# PRY417_Gde.net
KiCad netlist of a schematic drawn in EAGLE
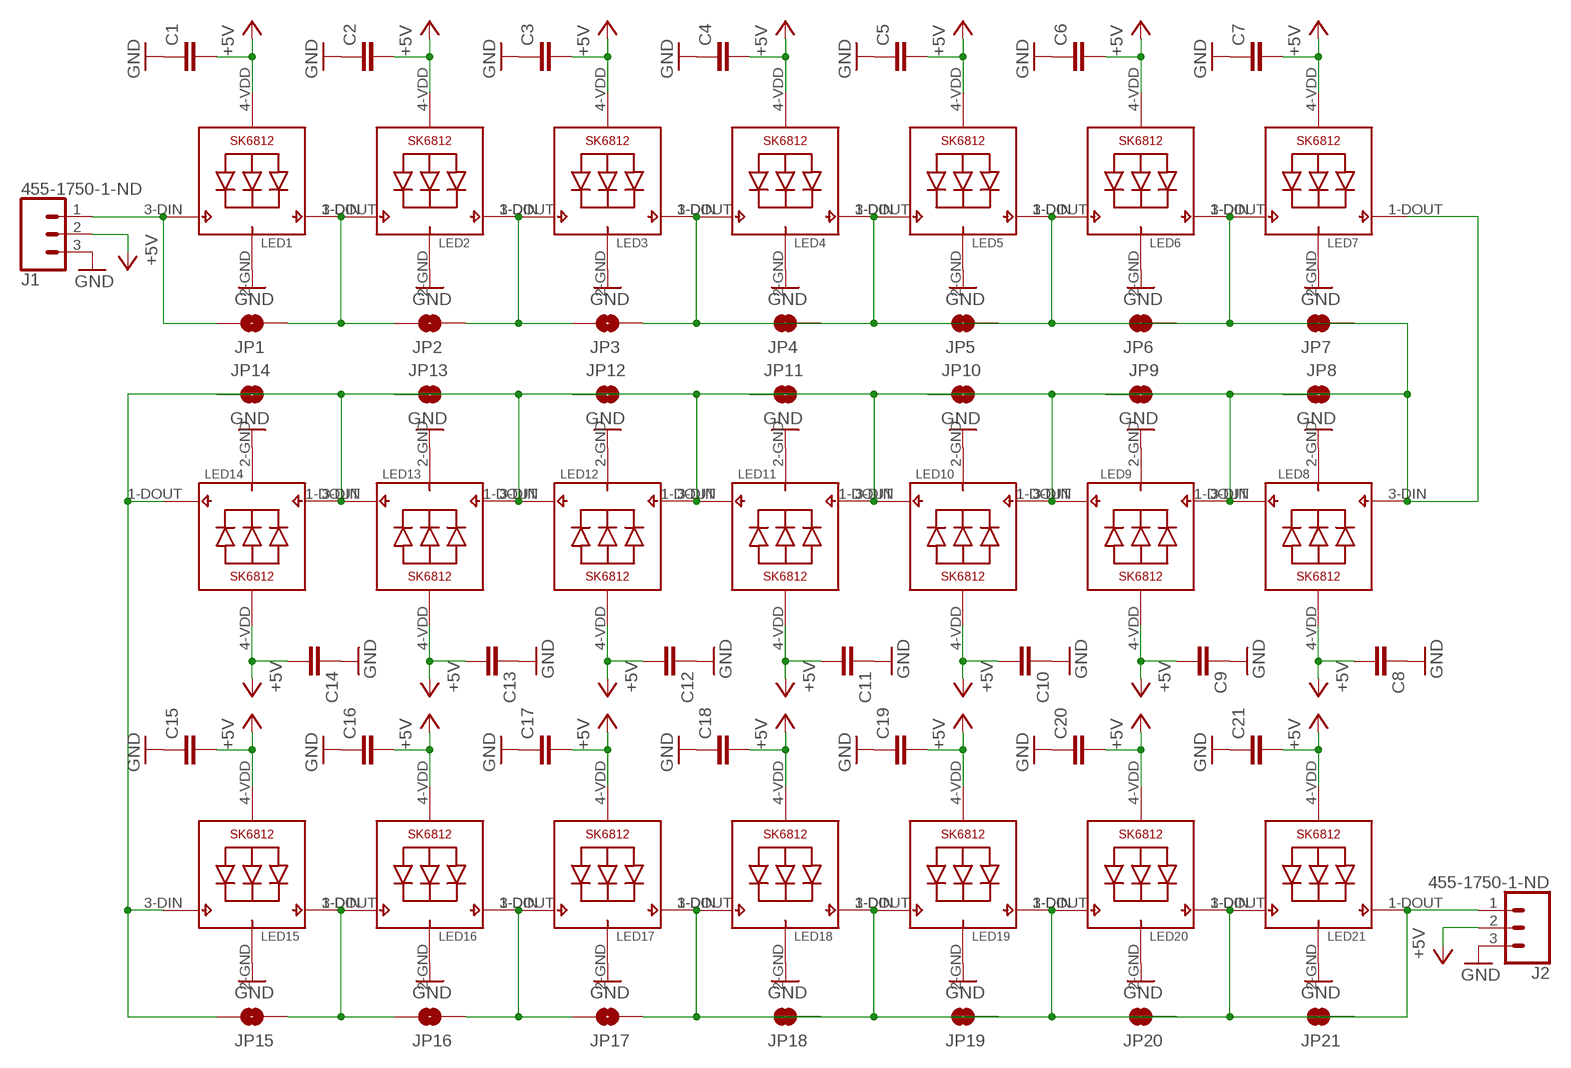
[diagram p0: schematic, sheet 1]

(export (version "E")
  (design (tool "Eeschema 10.0.6"))
  (components
    (comp (ref "C1")
      (value "C-EUC1206")
      (footprint "eagle-import:C1206")
      (libsource (lib "eagle-import") (part "C-EUC1206"))
    )
    (comp (ref "C2")
      (value "C-EUC1206")
      (footprint "eagle-import:C1206")
      (libsource (lib "eagle-import") (part "C-EUC1206"))
    )
    (comp (ref "C3")
      (value "C-EUC1206")
      (footprint "eagle-import:C1206")
      (libsource (lib "eagle-import") (part "C-EUC1206"))
    )
    (comp (ref "C4")
      (value "C-EUC1206")
      (footprint "eagle-import:C1206")
      (libsource (lib "eagle-import") (part "C-EUC1206"))
    )
    (comp (ref "C5")
      (value "C-EUC1206")
      (footprint "eagle-import:C1206")
      (libsource (lib "eagle-import") (part "C-EUC1206"))
    )
    (comp (ref "C6")
      (value "C-EUC1206")
      (footprint "eagle-import:C1206")
      (libsource (lib "eagle-import") (part "C-EUC1206"))
    )
    (comp (ref "C7")
      (value "C-EUC1206")
      (footprint "eagle-import:C1206")
      (libsource (lib "eagle-import") (part "C-EUC1206"))
    )
    (comp (ref "C8")
      (value "C-EUC1206")
      (footprint "eagle-import:C1206")
      (libsource (lib "eagle-import") (part "C-EUC1206"))
    )
    (comp (ref "C9")
      (value "C-EUC1206")
      (footprint "eagle-import:C1206")
      (libsource (lib "eagle-import") (part "C-EUC1206"))
    )
    (comp (ref "C10")
      (value "C-EUC1206")
      (footprint "eagle-import:C1206")
      (libsource (lib "eagle-import") (part "C-EUC1206"))
    )
    (comp (ref "C11")
      (value "C-EUC1206")
      (footprint "eagle-import:C1206")
      (libsource (lib "eagle-import") (part "C-EUC1206"))
    )
    (comp (ref "C12")
      (value "C-EUC1206")
      (footprint "eagle-import:C1206")
      (libsource (lib "eagle-import") (part "C-EUC1206"))
    )
    (comp (ref "C13")
      (value "C-EUC1206")
      (footprint "eagle-import:C1206")
      (libsource (lib "eagle-import") (part "C-EUC1206"))
    )
    (comp (ref "C14")
      (value "C-EUC1206")
      (footprint "eagle-import:C1206")
      (libsource (lib "eagle-import") (part "C-EUC1206"))
    )
    (comp (ref "C15")
      (value "C-EUC1206")
      (footprint "eagle-import:C1206")
      (libsource (lib "eagle-import") (part "C-EUC1206"))
    )
    (comp (ref "C16")
      (value "C-EUC1206")
      (footprint "eagle-import:C1206")
      (libsource (lib "eagle-import") (part "C-EUC1206"))
    )
    (comp (ref "C17")
      (value "C-EUC1206")
      (footprint "eagle-import:C1206")
      (libsource (lib "eagle-import") (part "C-EUC1206"))
    )
    (comp (ref "C18")
      (value "C-EUC1206")
      (footprint "eagle-import:C1206")
      (libsource (lib "eagle-import") (part "C-EUC1206"))
    )
    (comp (ref "C19")
      (value "C-EUC1206")
      (footprint "eagle-import:C1206")
      (libsource (lib "eagle-import") (part "C-EUC1206"))
    )
    (comp (ref "C20")
      (value "C-EUC1206")
      (footprint "eagle-import:C1206")
      (libsource (lib "eagle-import") (part "C-EUC1206"))
    )
    (comp (ref "C21")
      (value "C-EUC1206")
      (footprint "eagle-import:C1206")
      (libsource (lib "eagle-import") (part "C-EUC1206"))
    )
    (comp (ref "J1")
      (value "455-1750-1-ND")
      (footprint "eagle-import:1X03")
      (libsource (lib "eagle-import") (part "CONN_03"))
    )
    (comp (ref "J2")
      (value "455-1750-1-ND")
      (footprint "eagle-import:1X03")
      (libsource (lib "eagle-import") (part "CONN_03"))
    )
    (comp (ref "JP1")
      (value "JUMPER-SMT_2_NO_SILK")
      (footprint "eagle-import:SMT-JUMPER_2_NO_SILK")
      (libsource (lib "eagle-import") (part "JUMPER-SMT_2_NO_SILK"))
    )
    (comp (ref "JP2")
      (value "JUMPER-SMT_2_NO_SILK")
      (footprint "eagle-import:SMT-JUMPER_2_NO_SILK")
      (libsource (lib "eagle-import") (part "JUMPER-SMT_2_NO_SILK"))
    )
    (comp (ref "JP3")
      (value "JUMPER-SMT_2_NO_SILK")
      (footprint "eagle-import:SMT-JUMPER_2_NO_SILK")
      (libsource (lib "eagle-import") (part "JUMPER-SMT_2_NO_SILK"))
    )
    (comp (ref "JP4")
      (value "JUMPER-SMT_2_NO_SILK")
      (footprint "eagle-import:SMT-JUMPER_2_NO_SILK")
      (libsource (lib "eagle-import") (part "JUMPER-SMT_2_NO_SILK"))
    )
    (comp (ref "JP5")
      (value "JUMPER-SMT_2_NO_SILK")
      (footprint "eagle-import:SMT-JUMPER_2_NO_SILK")
      (libsource (lib "eagle-import") (part "JUMPER-SMT_2_NO_SILK"))
    )
    (comp (ref "JP6")
      (value "JUMPER-SMT_2_NO_SILK")
      (footprint "eagle-import:SMT-JUMPER_2_NO_SILK")
      (libsource (lib "eagle-import") (part "JUMPER-SMT_2_NO_SILK"))
    )
    (comp (ref "JP7")
      (value "JUMPER-SMT_2_NO_SILK")
      (footprint "eagle-import:SMT-JUMPER_2_NO_SILK")
      (libsource (lib "eagle-import") (part "JUMPER-SMT_2_NO_SILK"))
    )
    (comp (ref "JP8")
      (value "JUMPER-SMT_2_NO_SILK")
      (footprint "eagle-import:SMT-JUMPER_2_NO_SILK")
      (libsource (lib "eagle-import") (part "JUMPER-SMT_2_NO_SILK"))
    )
    (comp (ref "JP9")
      (value "JUMPER-SMT_2_NO_SILK")
      (footprint "eagle-import:SMT-JUMPER_2_NO_SILK")
      (libsource (lib "eagle-import") (part "JUMPER-SMT_2_NO_SILK"))
    )
    (comp (ref "JP10")
      (value "JUMPER-SMT_2_NO_SILK")
      (footprint "eagle-import:SMT-JUMPER_2_NO_SILK")
      (libsource (lib "eagle-import") (part "JUMPER-SMT_2_NO_SILK"))
    )
    (comp (ref "JP11")
      (value "JUMPER-SMT_2_NO_SILK")
      (footprint "eagle-import:SMT-JUMPER_2_NO_SILK")
      (libsource (lib "eagle-import") (part "JUMPER-SMT_2_NO_SILK"))
    )
    (comp (ref "JP12")
      (value "JUMPER-SMT_2_NO_SILK")
      (footprint "eagle-import:SMT-JUMPER_2_NO_SILK")
      (libsource (lib "eagle-import") (part "JUMPER-SMT_2_NO_SILK"))
    )
    (comp (ref "JP13")
      (value "JUMPER-SMT_2_NO_SILK")
      (footprint "eagle-import:SMT-JUMPER_2_NO_SILK")
      (libsource (lib "eagle-import") (part "JUMPER-SMT_2_NO_SILK"))
    )
    (comp (ref "JP14")
      (value "JUMPER-SMT_2_NO_SILK")
      (footprint "eagle-import:SMT-JUMPER_2_NO_SILK")
      (libsource (lib "eagle-import") (part "JUMPER-SMT_2_NO_SILK"))
    )
    (comp (ref "JP15")
      (value "JUMPER-SMT_2_NO_SILK")
      (footprint "eagle-import:SMT-JUMPER_2_NO_SILK")
      (libsource (lib "eagle-import") (part "JUMPER-SMT_2_NO_SILK"))
    )
    (comp (ref "JP16")
      (value "JUMPER-SMT_2_NO_SILK")
      (footprint "eagle-import:SMT-JUMPER_2_NO_SILK")
      (libsource (lib "eagle-import") (part "JUMPER-SMT_2_NO_SILK"))
    )
    (comp (ref "JP17")
      (value "JUMPER-SMT_2_NO_SILK")
      (footprint "eagle-import:SMT-JUMPER_2_NO_SILK")
      (libsource (lib "eagle-import") (part "JUMPER-SMT_2_NO_SILK"))
    )
    (comp (ref "JP18")
      (value "JUMPER-SMT_2_NO_SILK")
      (footprint "eagle-import:SMT-JUMPER_2_NO_SILK")
      (libsource (lib "eagle-import") (part "JUMPER-SMT_2_NO_SILK"))
    )
    (comp (ref "JP19")
      (value "JUMPER-SMT_2_NO_SILK")
      (footprint "eagle-import:SMT-JUMPER_2_NO_SILK")
      (libsource (lib "eagle-import") (part "JUMPER-SMT_2_NO_SILK"))
    )
    (comp (ref "JP20")
      (value "JUMPER-SMT_2_NO_SILK")
      (footprint "eagle-import:SMT-JUMPER_2_NO_SILK")
      (libsource (lib "eagle-import") (part "JUMPER-SMT_2_NO_SILK"))
    )
    (comp (ref "JP21")
      (value "JUMPER-SMT_2_NO_SILK")
      (footprint "eagle-import:SMT-JUMPER_2_NO_SILK")
      (libsource (lib "eagle-import") (part "JUMPER-SMT_2_NO_SILK"))
    )
    (comp (ref "LED1")
      (value "SK6812_3535")
      (footprint "eagle-import:LED3535")
      (libsource (lib "eagle-import") (part "SK6812_3535"))
    )
    (comp (ref "LED2")
      (value "SK6812_3535")
      (footprint "eagle-import:LED3535")
      (libsource (lib "eagle-import") (part "SK6812_3535"))
    )
    (comp (ref "LED3")
      (value "SK6812_3535")
      (footprint "eagle-import:LED3535")
      (libsource (lib "eagle-import") (part "SK6812_3535"))
    )
    (comp (ref "LED4")
      (value "SK6812_3535")
      (footprint "eagle-import:LED3535")
      (libsource (lib "eagle-import") (part "SK6812_3535"))
    )
    (comp (ref "LED5")
      (value "SK6812_3535")
      (footprint "eagle-import:LED3535")
      (libsource (lib "eagle-import") (part "SK6812_3535"))
    )
    (comp (ref "LED6")
      (value "SK6812_3535")
      (footprint "eagle-import:LED3535")
      (libsource (lib "eagle-import") (part "SK6812_3535"))
    )
    (comp (ref "LED7")
      (value "SK6812_3535")
      (footprint "eagle-import:LED3535")
      (libsource (lib "eagle-import") (part "SK6812_3535"))
    )
    (comp (ref "LED8")
      (value "SK6812_3535")
      (footprint "eagle-import:LED3535")
      (libsource (lib "eagle-import") (part "SK6812_3535"))
    )
    (comp (ref "LED9")
      (value "SK6812_3535")
      (footprint "eagle-import:LED3535")
      (libsource (lib "eagle-import") (part "SK6812_3535"))
    )
    (comp (ref "LED10")
      (value "SK6812_3535")
      (footprint "eagle-import:LED3535")
      (libsource (lib "eagle-import") (part "SK6812_3535"))
    )
    (comp (ref "LED11")
      (value "SK6812_3535")
      (footprint "eagle-import:LED3535")
      (libsource (lib "eagle-import") (part "SK6812_3535"))
    )
    (comp (ref "LED12")
      (value "SK6812_3535")
      (footprint "eagle-import:LED3535")
      (libsource (lib "eagle-import") (part "SK6812_3535"))
    )
    (comp (ref "LED13")
      (value "SK6812_3535")
      (footprint "eagle-import:LED3535")
      (libsource (lib "eagle-import") (part "SK6812_3535"))
    )
    (comp (ref "LED14")
      (value "SK6812_3535")
      (footprint "eagle-import:LED3535")
      (libsource (lib "eagle-import") (part "SK6812_3535"))
    )
    (comp (ref "LED15")
      (value "SK6812_3535")
      (footprint "eagle-import:LED3535")
      (libsource (lib "eagle-import") (part "SK6812_3535"))
    )
    (comp (ref "LED16")
      (value "SK6812_3535")
      (footprint "eagle-import:LED3535")
      (libsource (lib "eagle-import") (part "SK6812_3535"))
    )
    (comp (ref "LED17")
      (value "SK6812_3535")
      (footprint "eagle-import:LED3535")
      (libsource (lib "eagle-import") (part "SK6812_3535"))
    )
    (comp (ref "LED18")
      (value "SK6812_3535")
      (footprint "eagle-import:LED3535")
      (libsource (lib "eagle-import") (part "SK6812_3535"))
    )
    (comp (ref "LED19")
      (value "SK6812_3535")
      (footprint "eagle-import:LED3535")
      (libsource (lib "eagle-import") (part "SK6812_3535"))
    )
    (comp (ref "LED20")
      (value "SK6812_3535")
      (footprint "eagle-import:LED3535")
      (libsource (lib "eagle-import") (part "SK6812_3535"))
    )
    (comp (ref "LED21")
      (value "SK6812_3535")
      (footprint "eagle-import:LED3535")
      (libsource (lib "eagle-import") (part "SK6812_3535"))
    )
  )
  (nets
    (net (code "1") (name "+5V") (class "Default")
      (node (ref "C1") (pin "2") (pinfunction "2_2") (pintype "passive"))
      (node (ref "C10") (pin "2") (pinfunction "2_2") (pintype "passive"))
      (node (ref "C11") (pin "2") (pinfunction "2_2") (pintype "passive"))
      (node (ref "C12") (pin "2") (pinfunction "2_2") (pintype "passive"))
      (node (ref "C13") (pin "2") (pinfunction "2_2") (pintype "passive"))
      (node (ref "C14") (pin "2") (pinfunction "2_2") (pintype "passive"))
      (node (ref "C15") (pin "2") (pinfunction "2_2") (pintype "passive"))
      (node (ref "C16") (pin "2") (pinfunction "2_2") (pintype "passive"))
      (node (ref "C17") (pin "2") (pinfunction "2_2") (pintype "passive"))
      (node (ref "C18") (pin "2") (pinfunction "2_2") (pintype "passive"))
      (node (ref "C19") (pin "2") (pinfunction "2_2") (pintype "passive"))
      (node (ref "C2") (pin "2") (pinfunction "2_2") (pintype "passive"))
      (node (ref "C20") (pin "2") (pinfunction "2_2") (pintype "passive"))
      (node (ref "C21") (pin "2") (pinfunction "2_2") (pintype "passive"))
      (node (ref "C3") (pin "2") (pinfunction "2_2") (pintype "passive"))
      (node (ref "C4") (pin "2") (pinfunction "2_2") (pintype "passive"))
      (node (ref "C5") (pin "2") (pinfunction "2_2") (pintype "passive"))
      (node (ref "C6") (pin "2") (pinfunction "2_2") (pintype "passive"))
      (node (ref "C7") (pin "2") (pinfunction "2_2") (pintype "passive"))
      (node (ref "C8") (pin "2") (pinfunction "2_2") (pintype "passive"))
      (node (ref "C9") (pin "2") (pinfunction "2_2") (pintype "passive"))
      (node (ref "J1") (pin "2") (pinfunction "2_2") (pintype "passive"))
      (node (ref "J2") (pin "2") (pinfunction "2_2") (pintype "passive"))
      (node (ref "LED1") (pin "4-VDD") (pinfunction "VDD_4-VDD") (pintype "power_in"))
      (node (ref "LED10") (pin "4-VDD") (pinfunction "VDD_4-VDD") (pintype "power_in"))
      (node (ref "LED11") (pin "4-VDD") (pinfunction "VDD_4-VDD") (pintype "power_in"))
      (node (ref "LED12") (pin "4-VDD") (pinfunction "VDD_4-VDD") (pintype "power_in"))
      (node (ref "LED13") (pin "4-VDD") (pinfunction "VDD_4-VDD") (pintype "power_in"))
      (node (ref "LED14") (pin "4-VDD") (pinfunction "VDD_4-VDD") (pintype "power_in"))
      (node (ref "LED15") (pin "4-VDD") (pinfunction "VDD_4-VDD") (pintype "power_in"))
      (node (ref "LED16") (pin "4-VDD") (pinfunction "VDD_4-VDD") (pintype "power_in"))
      (node (ref "LED17") (pin "4-VDD") (pinfunction "VDD_4-VDD") (pintype "power_in"))
      (node (ref "LED18") (pin "4-VDD") (pinfunction "VDD_4-VDD") (pintype "power_in"))
      (node (ref "LED19") (pin "4-VDD") (pinfunction "VDD_4-VDD") (pintype "power_in"))
      (node (ref "LED2") (pin "4-VDD") (pinfunction "VDD_4-VDD") (pintype "power_in"))
      (node (ref "LED20") (pin "4-VDD") (pinfunction "VDD_4-VDD") (pintype "power_in"))
      (node (ref "LED21") (pin "4-VDD") (pinfunction "VDD_4-VDD") (pintype "power_in"))
      (node (ref "LED3") (pin "4-VDD") (pinfunction "VDD_4-VDD") (pintype "power_in"))
      (node (ref "LED4") (pin "4-VDD") (pinfunction "VDD_4-VDD") (pintype "power_in"))
      (node (ref "LED5") (pin "4-VDD") (pinfunction "VDD_4-VDD") (pintype "power_in"))
      (node (ref "LED6") (pin "4-VDD") (pinfunction "VDD_4-VDD") (pintype "power_in"))
      (node (ref "LED7") (pin "4-VDD") (pinfunction "VDD_4-VDD") (pintype "power_in"))
      (node (ref "LED8") (pin "4-VDD") (pinfunction "VDD_4-VDD") (pintype "power_in"))
      (node (ref "LED9") (pin "4-VDD") (pinfunction "VDD_4-VDD") (pintype "power_in"))
    )
    (net (code "2") (name "GND") (class "Default")
      (node (ref "C1") (pin "1") (pinfunction "1_1") (pintype "passive"))
      (node (ref "C10") (pin "1") (pinfunction "1_1") (pintype "passive"))
      (node (ref "C11") (pin "1") (pinfunction "1_1") (pintype "passive"))
      (node (ref "C12") (pin "1") (pinfunction "1_1") (pintype "passive"))
      (node (ref "C13") (pin "1") (pinfunction "1_1") (pintype "passive"))
      (node (ref "C14") (pin "1") (pinfunction "1_1") (pintype "passive"))
      (node (ref "C15") (pin "1") (pinfunction "1_1") (pintype "passive"))
      (node (ref "C16") (pin "1") (pinfunction "1_1") (pintype "passive"))
      (node (ref "C17") (pin "1") (pinfunction "1_1") (pintype "passive"))
      (node (ref "C18") (pin "1") (pinfunction "1_1") (pintype "passive"))
      (node (ref "C19") (pin "1") (pinfunction "1_1") (pintype "passive"))
      (node (ref "C2") (pin "1") (pinfunction "1_1") (pintype "passive"))
      (node (ref "C20") (pin "1") (pinfunction "1_1") (pintype "passive"))
      (node (ref "C21") (pin "1") (pinfunction "1_1") (pintype "passive"))
      (node (ref "C3") (pin "1") (pinfunction "1_1") (pintype "passive"))
      (node (ref "C4") (pin "1") (pinfunction "1_1") (pintype "passive"))
      (node (ref "C5") (pin "1") (pinfunction "1_1") (pintype "passive"))
      (node (ref "C6") (pin "1") (pinfunction "1_1") (pintype "passive"))
      (node (ref "C7") (pin "1") (pinfunction "1_1") (pintype "passive"))
      (node (ref "C8") (pin "1") (pinfunction "1_1") (pintype "passive"))
      (node (ref "C9") (pin "1") (pinfunction "1_1") (pintype "passive"))
      (node (ref "J1") (pin "3") (pinfunction "3_3") (pintype "passive"))
      (node (ref "J2") (pin "3") (pinfunction "3_3") (pintype "passive"))
      (node (ref "LED1") (pin "2-GND") (pinfunction "GND_2-GND") (pintype "power_in"))
      (node (ref "LED10") (pin "2-GND") (pinfunction "GND_2-GND") (pintype "power_in"))
      (node (ref "LED11") (pin "2-GND") (pinfunction "GND_2-GND") (pintype "power_in"))
      (node (ref "LED12") (pin "2-GND") (pinfunction "GND_2-GND") (pintype "power_in"))
      (node (ref "LED13") (pin "2-GND") (pinfunction "GND_2-GND") (pintype "power_in"))
      (node (ref "LED14") (pin "2-GND") (pinfunction "GND_2-GND") (pintype "power_in"))
      (node (ref "LED15") (pin "2-GND") (pinfunction "GND_2-GND") (pintype "power_in"))
      (node (ref "LED16") (pin "2-GND") (pinfunction "GND_2-GND") (pintype "power_in"))
      (node (ref "LED17") (pin "2-GND") (pinfunction "GND_2-GND") (pintype "power_in"))
      (node (ref "LED18") (pin "2-GND") (pinfunction "GND_2-GND") (pintype "power_in"))
      (node (ref "LED19") (pin "2-GND") (pinfunction "GND_2-GND") (pintype "power_in"))
      (node (ref "LED2") (pin "2-GND") (pinfunction "GND_2-GND") (pintype "power_in"))
      (node (ref "LED20") (pin "2-GND") (pinfunction "GND_2-GND") (pintype "power_in"))
      (node (ref "LED21") (pin "2-GND") (pinfunction "GND_2-GND") (pintype "power_in"))
      (node (ref "LED3") (pin "2-GND") (pinfunction "GND_2-GND") (pintype "power_in"))
      (node (ref "LED4") (pin "2-GND") (pinfunction "GND_2-GND") (pintype "power_in"))
      (node (ref "LED5") (pin "2-GND") (pinfunction "GND_2-GND") (pintype "power_in"))
      (node (ref "LED6") (pin "2-GND") (pinfunction "GND_2-GND") (pintype "power_in"))
      (node (ref "LED7") (pin "2-GND") (pinfunction "GND_2-GND") (pintype "power_in"))
      (node (ref "LED8") (pin "2-GND") (pinfunction "GND_2-GND") (pintype "power_in"))
      (node (ref "LED9") (pin "2-GND") (pinfunction "GND_2-GND") (pintype "power_in"))
    )
    (net (code "3") (name "Net-(LED1-DI)") (class "Default")
      (node (ref "J1") (pin "1") (pinfunction "1_1") (pintype "passive"))
      (node (ref "JP1") (pin "1") (pinfunction "1_1") (pintype "passive"))
      (node (ref "LED1") (pin "3-DIN") (pinfunction "DI_3-DIN") (pintype "input"))
    )
    (net (code "4") (name "Net-(LED1-DO)") (class "Default")
      (node (ref "JP1") (pin "2") (pinfunction "2_2") (pintype "passive"))
      (node (ref "JP2") (pin "1") (pinfunction "1_1") (pintype "passive"))
      (node (ref "LED1") (pin "1-DOUT") (pinfunction "DO_1-DOUT") (pintype "output"))
      (node (ref "LED2") (pin "3-DIN") (pinfunction "DI_3-DIN") (pintype "input"))
    )
    (net (code "5") (name "Net-(LED2-DO)") (class "Default")
      (node (ref "JP2") (pin "2") (pinfunction "2_2") (pintype "passive"))
      (node (ref "JP3") (pin "1") (pinfunction "1_1") (pintype "passive"))
      (node (ref "LED2") (pin "1-DOUT") (pinfunction "DO_1-DOUT") (pintype "output"))
      (node (ref "LED3") (pin "3-DIN") (pinfunction "DI_3-DIN") (pintype "input"))
    )
    (net (code "6") (name "Net-(LED3-DO)") (class "Default")
      (node (ref "JP3") (pin "2") (pinfunction "2_2") (pintype "passive"))
      (node (ref "JP4") (pin "2") (pinfunction "2_2") (pintype "passive"))
      (node (ref "LED3") (pin "1-DOUT") (pinfunction "DO_1-DOUT") (pintype "output"))
      (node (ref "LED4") (pin "3-DIN") (pinfunction "DI_3-DIN") (pintype "input"))
    )
    (net (code "7") (name "Net-(LED4-DO)") (class "Default")
      (node (ref "JP4") (pin "1") (pinfunction "1_1") (pintype "passive"))
      (node (ref "JP5") (pin "2") (pinfunction "2_2") (pintype "passive"))
      (node (ref "LED4") (pin "1-DOUT") (pinfunction "DO_1-DOUT") (pintype "output"))
      (node (ref "LED5") (pin "3-DIN") (pinfunction "DI_3-DIN") (pintype "input"))
    )
    (net (code "8") (name "Net-(LED5-DO)") (class "Default")
      (node (ref "JP5") (pin "1") (pinfunction "1_1") (pintype "passive"))
      (node (ref "JP6") (pin "2") (pinfunction "2_2") (pintype "passive"))
      (node (ref "LED5") (pin "1-DOUT") (pinfunction "DO_1-DOUT") (pintype "output"))
      (node (ref "LED6") (pin "3-DIN") (pinfunction "DI_3-DIN") (pintype "input"))
    )
    (net (code "9") (name "Net-(LED6-DO)") (class "Default")
      (node (ref "JP6") (pin "1") (pinfunction "1_1") (pintype "passive"))
      (node (ref "JP7") (pin "2") (pinfunction "2_2") (pintype "passive"))
      (node (ref "LED6") (pin "1-DOUT") (pinfunction "DO_1-DOUT") (pintype "output"))
      (node (ref "LED7") (pin "3-DIN") (pinfunction "DI_3-DIN") (pintype "input"))
    )
    (net (code "10") (name "Net-(LED7-DO)") (class "Default")
      (node (ref "JP7") (pin "1") (pinfunction "1_1") (pintype "passive"))
      (node (ref "JP8") (pin "2") (pinfunction "2_2") (pintype "passive"))
      (node (ref "LED7") (pin "1-DOUT") (pinfunction "DO_1-DOUT") (pintype "output"))
      (node (ref "LED8") (pin "3-DIN") (pinfunction "DI_3-DIN") (pintype "input"))
    )
    (net (code "11") (name "Net-(LED8-DO)") (class "Default")
      (node (ref "JP8") (pin "1") (pinfunction "1_1") (pintype "passive"))
      (node (ref "JP9") (pin "2") (pinfunction "2_2") (pintype "passive"))
      (node (ref "LED8") (pin "1-DOUT") (pinfunction "DO_1-DOUT") (pintype "output"))
      (node (ref "LED9") (pin "3-DIN") (pinfunction "DI_3-DIN") (pintype "input"))
    )
    (net (code "12") (name "Net-(LED10-DI)") (class "Default")
      (node (ref "JP10") (pin "2") (pinfunction "2_2") (pintype "passive"))
      (node (ref "JP9") (pin "1") (pinfunction "1_1") (pintype "passive"))
      (node (ref "LED10") (pin "3-DIN") (pinfunction "DI_3-DIN") (pintype "input"))
      (node (ref "LED9") (pin "1-DOUT") (pinfunction "DO_1-DOUT") (pintype "output"))
    )
    (net (code "13") (name "Net-(LED10-DO)") (class "Default")
      (node (ref "JP10") (pin "1") (pinfunction "1_1") (pintype "passive"))
      (node (ref "JP11") (pin "2") (pinfunction "2_2") (pintype "passive"))
      (node (ref "LED10") (pin "1-DOUT") (pinfunction "DO_1-DOUT") (pintype "output"))
      (node (ref "LED11") (pin "3-DIN") (pinfunction "DI_3-DIN") (pintype "input"))
    )
    (net (code "14") (name "Net-(LED11-DO)") (class "Default")
      (node (ref "JP11") (pin "1") (pinfunction "1_1") (pintype "passive"))
      (node (ref "JP12") (pin "2") (pinfunction "2_2") (pintype "passive"))
      (node (ref "LED11") (pin "1-DOUT") (pinfunction "DO_1-DOUT") (pintype "output"))
      (node (ref "LED12") (pin "3-DIN") (pinfunction "DI_3-DIN") (pintype "input"))
    )
    (net (code "15") (name "Net-(LED12-DO)") (class "Default")
      (node (ref "JP12") (pin "1") (pinfunction "1_1") (pintype "passive"))
      (node (ref "JP13") (pin "2") (pinfunction "2_2") (pintype "passive"))
      (node (ref "LED12") (pin "1-DOUT") (pinfunction "DO_1-DOUT") (pintype "output"))
      (node (ref "LED13") (pin "3-DIN") (pinfunction "DI_3-DIN") (pintype "input"))
    )
    (net (code "16") (name "Net-(LED13-DO)") (class "Default")
      (node (ref "JP13") (pin "1") (pinfunction "1_1") (pintype "passive"))
      (node (ref "JP14") (pin "2") (pinfunction "2_2") (pintype "passive"))
      (node (ref "LED13") (pin "1-DOUT") (pinfunction "DO_1-DOUT") (pintype "output"))
      (node (ref "LED14") (pin "3-DIN") (pinfunction "DI_3-DIN") (pintype "input"))
    )
    (net (code "17") (name "Net-(LED14-DO)") (class "Default")
      (node (ref "JP14") (pin "1") (pinfunction "1_1") (pintype "passive"))
      (node (ref "JP15") (pin "1") (pinfunction "1_1") (pintype "passive"))
      (node (ref "LED14") (pin "1-DOUT") (pinfunction "DO_1-DOUT") (pintype "output"))
      (node (ref "LED15") (pin "3-DIN") (pinfunction "DI_3-DIN") (pintype "input"))
    )
    (net (code "18") (name "Net-(LED15-DO)") (class "Default")
      (node (ref "JP15") (pin "2") (pinfunction "2_2") (pintype "passive"))
      (node (ref "JP16") (pin "1") (pinfunction "1_1") (pintype "passive"))
      (node (ref "LED15") (pin "1-DOUT") (pinfunction "DO_1-DOUT") (pintype "output"))
      (node (ref "LED16") (pin "3-DIN") (pinfunction "DI_3-DIN") (pintype "input"))
    )
    (net (code "19") (name "Net-(LED16-DO)") (class "Default")
      (node (ref "JP16") (pin "2") (pinfunction "2_2") (pintype "passive"))
      (node (ref "JP17") (pin "1") (pinfunction "1_1") (pintype "passive"))
      (node (ref "LED16") (pin "1-DOUT") (pinfunction "DO_1-DOUT") (pintype "output"))
      (node (ref "LED17") (pin "3-DIN") (pinfunction "DI_3-DIN") (pintype "input"))
    )
    (net (code "20") (name "Net-(LED17-DO)") (class "Default")
      (node (ref "JP17") (pin "2") (pinfunction "2_2") (pintype "passive"))
      (node (ref "JP18") (pin "2") (pinfunction "2_2") (pintype "passive"))
      (node (ref "LED17") (pin "1-DOUT") (pinfunction "DO_1-DOUT") (pintype "output"))
      (node (ref "LED18") (pin "3-DIN") (pinfunction "DI_3-DIN") (pintype "input"))
    )
    (net (code "21") (name "Net-(LED18-DO)") (class "Default")
      (node (ref "JP18") (pin "1") (pinfunction "1_1") (pintype "passive"))
      (node (ref "JP19") (pin "2") (pinfunction "2_2") (pintype "passive"))
      (node (ref "LED18") (pin "1-DOUT") (pinfunction "DO_1-DOUT") (pintype "output"))
      (node (ref "LED19") (pin "3-DIN") (pinfunction "DI_3-DIN") (pintype "input"))
    )
    (net (code "22") (name "Net-(LED19-DO)") (class "Default")
      (node (ref "JP19") (pin "1") (pinfunction "1_1") (pintype "passive"))
      (node (ref "JP20") (pin "2") (pinfunction "2_2") (pintype "passive"))
      (node (ref "LED19") (pin "1-DOUT") (pinfunction "DO_1-DOUT") (pintype "output"))
      (node (ref "LED20") (pin "3-DIN") (pinfunction "DI_3-DIN") (pintype "input"))
    )
    (net (code "23") (name "Net-(LED20-DO)") (class "Default")
      (node (ref "JP20") (pin "1") (pinfunction "1_1") (pintype "passive"))
      (node (ref "JP21") (pin "2") (pinfunction "2_2") (pintype "passive"))
      (node (ref "LED20") (pin "1-DOUT") (pinfunction "DO_1-DOUT") (pintype "output"))
      (node (ref "LED21") (pin "3-DIN") (pinfunction "DI_3-DIN") (pintype "input"))
    )
    (net (code "24") (name "Net-(LED21-DO)") (class "Default")
      (node (ref "J2") (pin "1") (pinfunction "1_1") (pintype "passive"))
      (node (ref "JP21") (pin "1") (pinfunction "1_1") (pintype "passive"))
      (node (ref "LED21") (pin "1-DOUT") (pinfunction "DO_1-DOUT") (pintype "output"))
    )
  )
)
